# solenoid_driver_RJ45_1_0.net
KiCad netlist of a schematic drawn in EAGLE
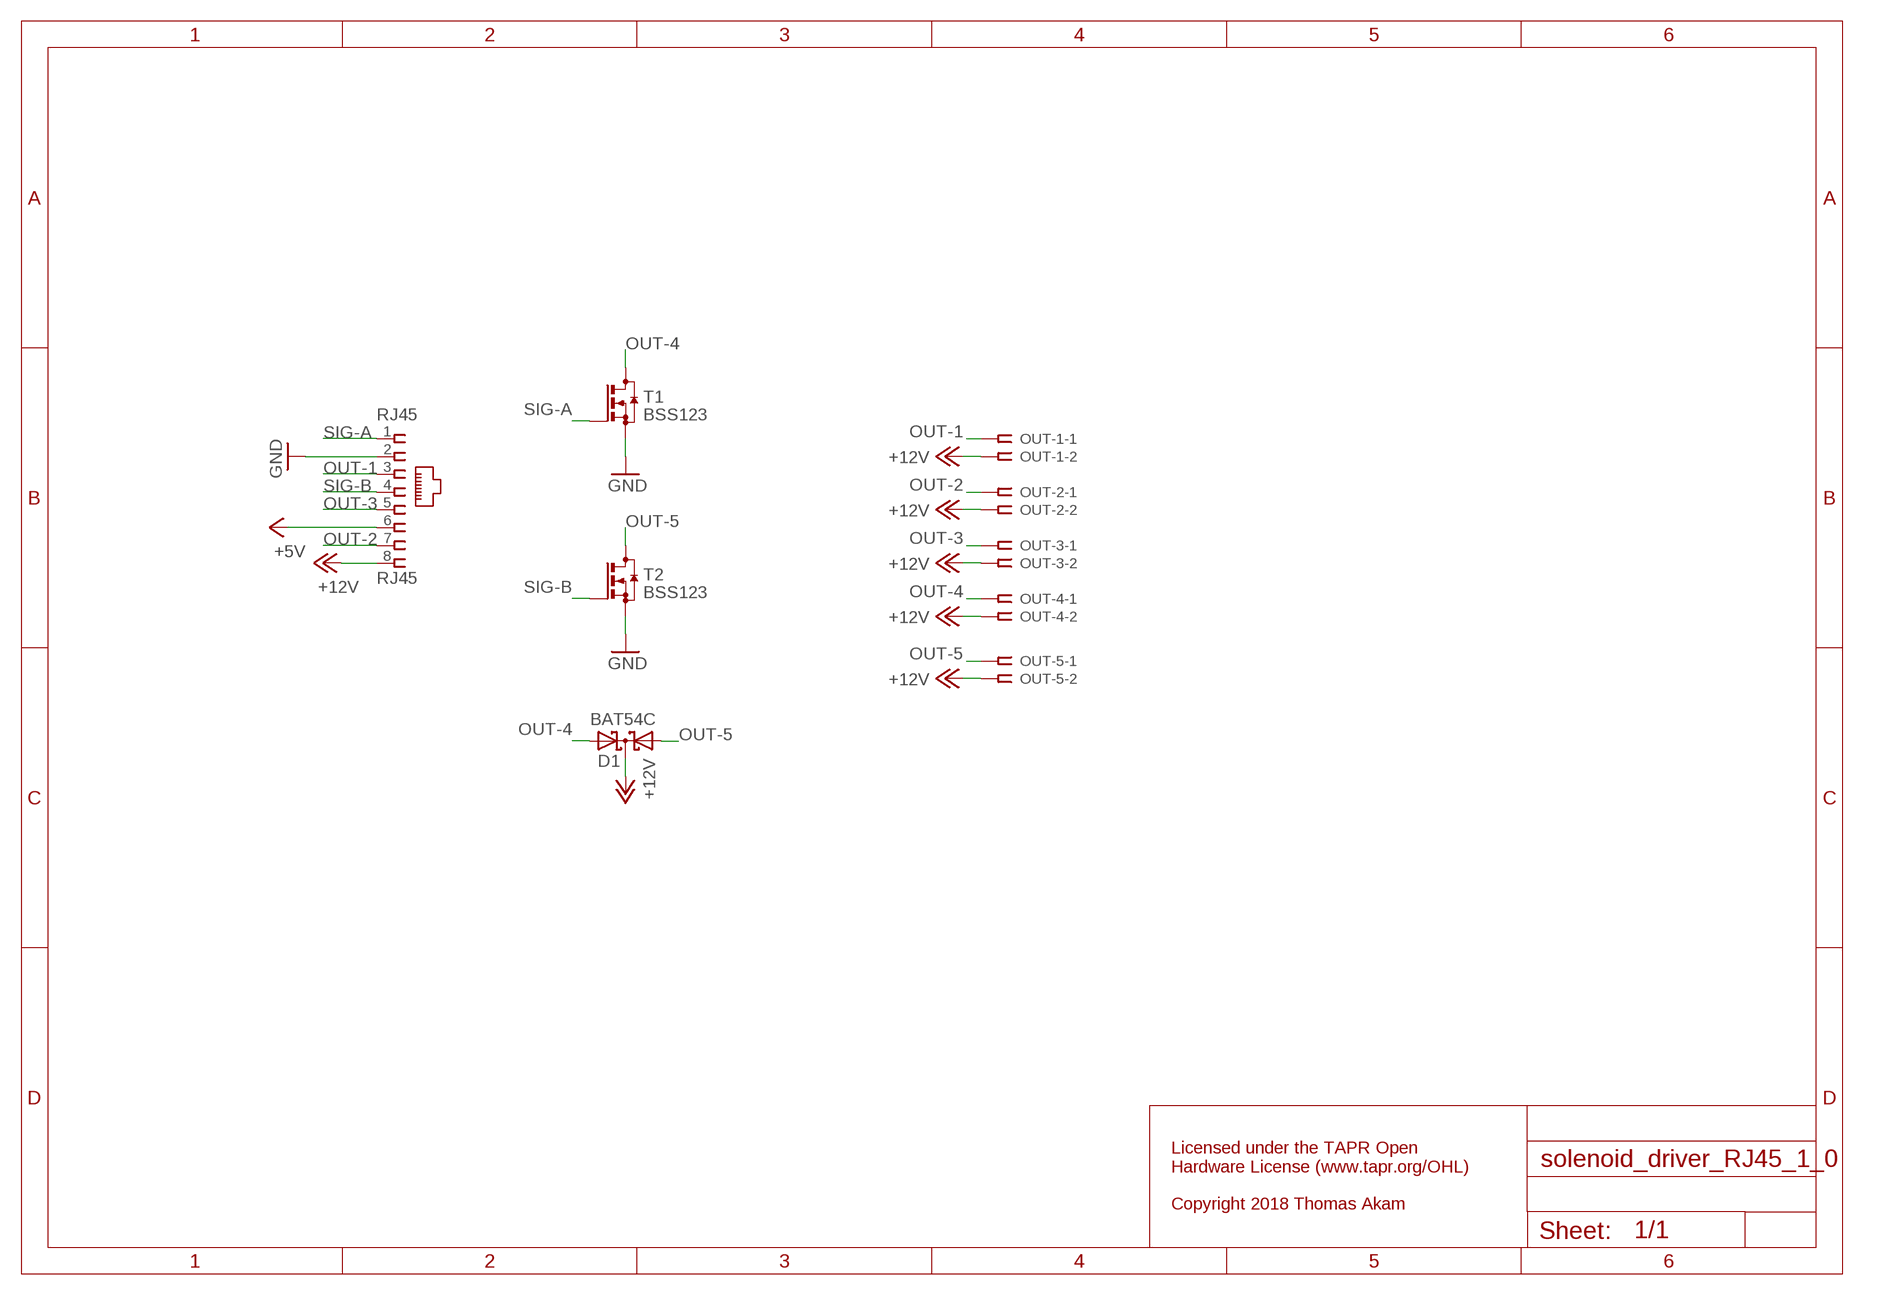
[diagram p0: schematic, sheet 1]

(export (version "E")
  (design (tool "Eeschema 10.0.6"))
  (components
    (comp (ref "D1")
      (value "BAT54C")
      (footprint "eagle-import:SOT23")
      (libsource (lib "eagle-import") (part "BAT54C"))
    )
    (comp (ref "OUT-1")
      (value "SSW-102-02-S-S-RA")
      (footprint "eagle-import:SSW-102-02-S-S-RA")
      (libsource (lib "eagle-import") (part "SSW-102-02-S-S-RA"))
    )
    (comp (ref "OUT-2")
      (value "SSW-102-02-S-S-RA")
      (footprint "eagle-import:SSW-102-02-S-S-RA")
      (libsource (lib "eagle-import") (part "SSW-102-02-S-S-RA"))
    )
    (comp (ref "OUT-3")
      (value "SSW-102-02-S-S-RA")
      (footprint "eagle-import:SSW-102-02-S-S-RA")
      (libsource (lib "eagle-import") (part "SSW-102-02-S-S-RA"))
    )
    (comp (ref "OUT-4")
      (value "SSW-102-02-S-S-RA")
      (footprint "eagle-import:SSW-102-02-S-S-RA")
      (libsource (lib "eagle-import") (part "SSW-102-02-S-S-RA"))
    )
    (comp (ref "OUT-5")
      (value "SSW-102-02-S-S-RA")
      (footprint "eagle-import:SSW-102-02-S-S-RA")
      (libsource (lib "eagle-import") (part "SSW-102-02-S-S-RA"))
    )
    (comp (ref "RJ45")
      (value "RJ45")
      (footprint "eagle-import:RJ45-NO-SHIELD-VERTICAL")
      (libsource (lib "eagle-import") (part "RJ45VERTICAL"))
    )
    (comp (ref "T1")
      (value "BSS123")
      (footprint "eagle-import:SOT23")
      (libsource (lib "eagle-import") (part "BSS123"))
    )
    (comp (ref "T2")
      (value "BSS123")
      (footprint "eagle-import:SOT23")
      (libsource (lib "eagle-import") (part "BSS123"))
    )
  )
  (nets
    (net (code "1") (name "+5V") (class "Default")
      (node (ref "RJ45") (pin "6") (pinfunction "6_6") (pintype "passive"))
    )
    (net (code "2") (name "+12V") (class "Default")
      (node (ref "D1") (pin "3") (pinfunction "CC_3") (pintype "passive"))
      (node (ref "OUT-1") (pin "2") (pinfunction "1_2") (pintype "passive"))
      (node (ref "OUT-2") (pin "2") (pinfunction "1_2") (pintype "passive"))
      (node (ref "OUT-3") (pin "2") (pinfunction "1_2") (pintype "passive"))
      (node (ref "OUT-4") (pin "2") (pinfunction "1_2") (pintype "passive"))
      (node (ref "OUT-5") (pin "2") (pinfunction "1_2") (pintype "passive"))
      (node (ref "RJ45") (pin "8") (pinfunction "8_8") (pintype "passive"))
    )
    (net (code "3") (name "/OUT-1") (class "Default")
      (node (ref "OUT-1") (pin "1") (pinfunction "1_1") (pintype "passive"))
      (node (ref "RJ45") (pin "3") (pinfunction "3_3") (pintype "passive"))
    )
    (net (code "4") (name "/OUT-2") (class "Default")
      (node (ref "OUT-2") (pin "1") (pinfunction "1_1") (pintype "passive"))
      (node (ref "RJ45") (pin "7") (pinfunction "7_7") (pintype "passive"))
    )
    (net (code "5") (name "/OUT-3") (class "Default")
      (node (ref "OUT-3") (pin "1") (pinfunction "1_1") (pintype "passive"))
      (node (ref "RJ45") (pin "5") (pinfunction "5_5") (pintype "passive"))
    )
    (net (code "6") (name "/OUT-4") (class "Default")
      (node (ref "D1") (pin "2") (pinfunction "A2_2") (pintype "passive"))
      (node (ref "OUT-4") (pin "1") (pinfunction "1_1") (pintype "passive"))
      (node (ref "T1") (pin "3") (pinfunction "D_3") (pintype "passive"))
    )
    (net (code "7") (name "/OUT-5") (class "Default")
      (node (ref "D1") (pin "1") (pinfunction "A1_1") (pintype "passive"))
      (node (ref "OUT-5") (pin "1") (pinfunction "1_1") (pintype "passive"))
      (node (ref "T2") (pin "3") (pinfunction "D_3") (pintype "passive"))
    )
    (net (code "8") (name "/SIG-A") (class "Default")
      (node (ref "RJ45") (pin "1") (pinfunction "1_1") (pintype "passive"))
      (node (ref "T1") (pin "1") (pinfunction "G_1") (pintype "passive"))
    )
    (net (code "9") (name "/SIG-B") (class "Default")
      (node (ref "RJ45") (pin "4") (pinfunction "4_4") (pintype "passive"))
      (node (ref "T2") (pin "1") (pinfunction "G_1") (pintype "passive"))
    )
    (net (code "10") (name "GND") (class "Default")
      (node (ref "RJ45") (pin "2") (pinfunction "2_2") (pintype "passive"))
      (node (ref "T1") (pin "2") (pinfunction "S_2") (pintype "passive"))
      (node (ref "T2") (pin "2") (pinfunction "S_2") (pintype "passive"))
    )
  )
)
